# Modular-v1.net
KiCad netlist of a schematic drawn in EAGLE
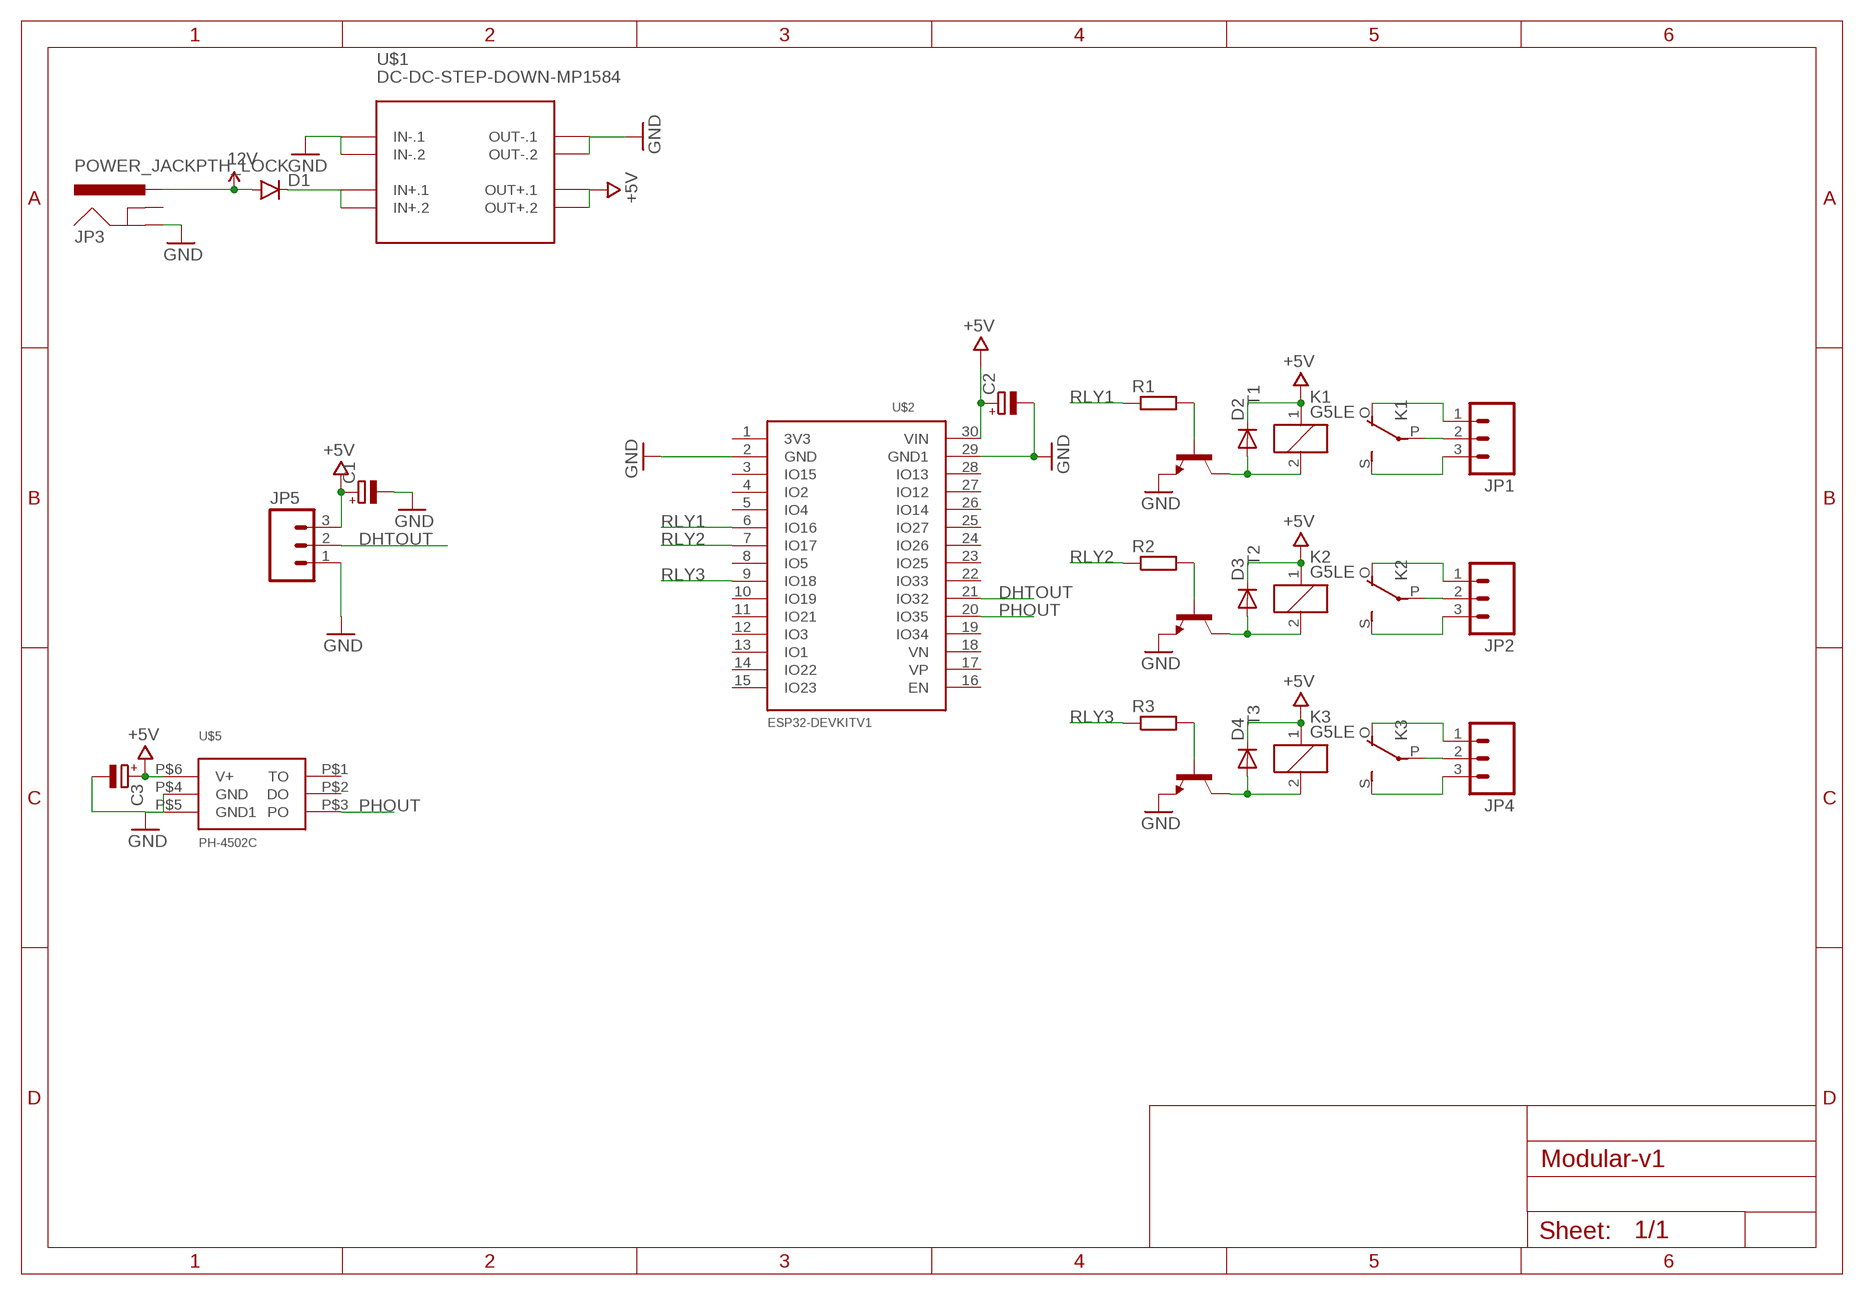
[diagram p0: schematic, sheet 1]

(export (version "E")
  (design (tool "Eeschema 10.0.6"))
  (components
    (comp (ref "C1")
      (value "CPOL-EUE5-5")
      (footprint "eagle-import:E5-5")
      (libsource (lib "eagle-import") (part "CPOL-EUE5-5"))
    )
    (comp (ref "C2")
      (value "CPOL-EUE5-13")
      (footprint "eagle-import:E5-13")
      (libsource (lib "eagle-import") (part "CPOL-EUE5-13"))
    )
    (comp (ref "C3")
      (value "CPOL-EUE5-8.5")
      (footprint "eagle-import:E5-8,5")
      (libsource (lib "eagle-import") (part "CPOL-EUE5-8.5"))
    )
    (comp (ref "D1")
      (value "DIODEKIT")
      (footprint "eagle-import:DIODE-1N4148-KIT")
      (libsource (lib "eagle-import") (part "DIODEKIT"))
    )
    (comp (ref "D2")
      (value "DIODE-D-2.5")
      (footprint "eagle-import:D-2.5")
      (libsource (lib "eagle-import") (part "DIODE-D-2.5"))
    )
    (comp (ref "D3")
      (value "DIODE-D-2.5")
      (footprint "eagle-import:D-2.5")
      (libsource (lib "eagle-import") (part "DIODE-D-2.5"))
    )
    (comp (ref "D4")
      (value "DIODE-D-2.5")
      (footprint "eagle-import:D-2.5")
      (libsource (lib "eagle-import") (part "DIODE-D-2.5"))
    )
    (comp (ref "JP1")
      (value "M03-SCREW-5MM")
      (footprint "eagle-import:SCREWTERMINAL-5MM-3")
      (libsource (lib "eagle-import") (part "M03-SCREW-5MM"))
    )
    (comp (ref "JP2")
      (value "M03-SCREW-5MM")
      (footprint "eagle-import:SCREWTERMINAL-5MM-3")
      (libsource (lib "eagle-import") (part "M03-SCREW-5MM"))
    )
    (comp (ref "JP3")
      (value "POWER_JACKPTH_LOCK")
      (footprint "eagle-import:POWER_JACK_PTH_LOCK")
      (libsource (lib "eagle-import") (part "POWER_JACKPTH_LOCK"))
    )
    (comp (ref "JP4")
      (value "M03-SCREW-5MM")
      (footprint "eagle-import:SCREWTERMINAL-5MM-3")
      (libsource (lib "eagle-import") (part "M03-SCREW-5MM"))
    )
    (comp (ref "JP5")
      (value "M03-SCREW-5MM")
      (footprint "eagle-import:SCREWTERMINAL-5MM-3")
      (libsource (lib "eagle-import") (part "M03-SCREW-5MM"))
    )
    (comp (ref "K1")
      (value "G5LE")
      (footprint "eagle-import:G5LE")
      (libsource (lib "eagle-import") (part "G5LE"))
    )
    (comp (ref "K2")
      (value "G5LE")
      (footprint "eagle-import:G5LE")
      (libsource (lib "eagle-import") (part "G5LE"))
    )
    (comp (ref "K3")
      (value "G5LE")
      (footprint "eagle-import:G5LE")
      (libsource (lib "eagle-import") (part "G5LE"))
    )
    (comp (ref "R1")
      (value "R-EU_R0805")
      (footprint "eagle-import:R0805")
      (libsource (lib "eagle-import") (part "R-EU_R0805"))
    )
    (comp (ref "R2")
      (value "R-EU_R0805")
      (footprint "eagle-import:R0805")
      (libsource (lib "eagle-import") (part "R-EU_R0805"))
    )
    (comp (ref "R3")
      (value "R-EU_R0805")
      (footprint "eagle-import:R0805")
      (libsource (lib "eagle-import") (part "R-EU_R0805"))
    )
    (comp (ref "T1")
      (value "-NPN-TO92-EBC")
      (footprint "eagle-import:TO92-EBC")
      (libsource (lib "eagle-import") (part "-NPN-TO92-EBC"))
    )
    (comp (ref "T2")
      (value "-NPN-TO92-EBC")
      (footprint "eagle-import:TO92-EBC")
      (libsource (lib "eagle-import") (part "-NPN-TO92-EBC"))
    )
    (comp (ref "T3")
      (value "-NPN-TO92-EBC")
      (footprint "eagle-import:TO92-EBC")
      (libsource (lib "eagle-import") (part "-NPN-TO92-EBC"))
    )
    (comp (ref "U$1")
      (value "DC-DC-STEP-DOWN-MP1584")
      (footprint "eagle-import:DC-DC-STEP-DOWN-MP1584")
      (libsource (lib "eagle-import") (part "DC-DC-STEP-DOWN-MP1584"))
    )
    (comp (ref "U$2")
      (value "ESP32DEVKITV1")
      (footprint "eagle-import:ESP32-DEVKITV1")
      (libsource (lib "eagle-import") (part "ESP32DEVKITV1"))
    )
    (comp (ref "U$5")
      (value "PH-4502C")
      (footprint "eagle-import:PH-4502C")
      (libsource (lib "eagle-import") (part "PH-4502C"))
    )
  )
  (nets
    (net (code "1") (name "+5V") (class "Default")
      (node (ref "C1") (pin "+") (pinfunction "+_+") (pintype "passive"))
      (node (ref "C2") (pin "+") (pinfunction "+_+") (pintype "passive"))
      (node (ref "C3") (pin "+") (pinfunction "+_+") (pintype "passive"))
      (node (ref "D2") (pin "C") (pinfunction "C_C") (pintype "passive"))
      (node (ref "D3") (pin "C") (pinfunction "C_C") (pintype "passive"))
      (node (ref "D4") (pin "C") (pinfunction "C_C") (pintype "passive"))
      (node (ref "JP5") (pin "3") (pinfunction "3_3") (pintype "passive"))
      (node (ref "K1") (pin "1") (pinfunction "1_1") (pintype "passive"))
      (node (ref "K2") (pin "1") (pinfunction "1_1") (pintype "passive"))
      (node (ref "K3") (pin "1") (pinfunction "1_1") (pintype "passive"))
      (node (ref "U$1") (pin "OUT+.1") (pinfunction "OUT+.1_OUT+.1") (pintype "bidirectional"))
      (node (ref "U$1") (pin "OUT+.2") (pinfunction "OUT+.2_OUT+.2") (pintype "bidirectional"))
      (node (ref "U$2") (pin "30") (pinfunction "VIN_30") (pintype "bidirectional"))
      (node (ref "U$5") (pin "P$6") (pinfunction "V+_P$6") (pintype "bidirectional"))
    )
    (net (code "2") (name "/DHTOUT") (class "Default")
      (node (ref "JP5") (pin "2") (pinfunction "2_2") (pintype "passive"))
      (node (ref "U$2") (pin "21") (pinfunction "IO32_21") (pintype "bidirectional"))
    )
    (net (code "3") (name "/PHOUT") (class "Default")
      (node (ref "U$2") (pin "20") (pinfunction "IO35_20") (pintype "bidirectional"))
      (node (ref "U$5") (pin "P$3") (pinfunction "PO_P$3") (pintype "bidirectional"))
    )
    (net (code "4") (name "/RLY1") (class "Default")
      (node (ref "R1") (pin "1") (pinfunction "1_1") (pintype "passive"))
      (node (ref "U$2") (pin "6") (pinfunction "IO16_6") (pintype "bidirectional"))
    )
    (net (code "5") (name "/RLY2") (class "Default")
      (node (ref "R2") (pin "1") (pinfunction "1_1") (pintype "passive"))
      (node (ref "U$2") (pin "7") (pinfunction "IO17_7") (pintype "bidirectional"))
    )
    (net (code "6") (name "/RLY3") (class "Default")
      (node (ref "R3") (pin "1") (pinfunction "1_1") (pintype "passive"))
      (node (ref "U$2") (pin "9") (pinfunction "IO18_9") (pintype "bidirectional"))
    )
    (net (code "7") (name "12V") (class "Default")
      (node (ref "D1") (pin "A") (pinfunction "A_A") (pintype "passive"))
      (node (ref "JP3") (pin "PWR") (pinfunction "PWR_PWR") (pintype "bidirectional"))
    )
    (net (code "8") (name "GND") (class "Default")
      (node (ref "C1") (pin "-") (pinfunction "-_-") (pintype "passive"))
      (node (ref "C2") (pin "-") (pinfunction "-_-") (pintype "passive"))
      (node (ref "C3") (pin "-") (pinfunction "-_-") (pintype "passive"))
      (node (ref "JP3") (pin "GND") (pinfunction "GND_GND") (pintype "bidirectional"))
      (node (ref "JP5") (pin "1") (pinfunction "1_1") (pintype "passive"))
      (node (ref "T1") (pin "E") (pinfunction "E_E") (pintype "passive"))
      (node (ref "T2") (pin "E") (pinfunction "E_E") (pintype "passive"))
      (node (ref "T3") (pin "E") (pinfunction "E_E") (pintype "passive"))
      (node (ref "U$1") (pin "IN-.1") (pinfunction "IN-.1_IN-.1") (pintype "bidirectional"))
      (node (ref "U$1") (pin "IN-.2") (pinfunction "IN-.2_IN-.2") (pintype "bidirectional"))
      (node (ref "U$1") (pin "OUT-.1") (pinfunction "OUT-.1_OUT-.1") (pintype "bidirectional"))
      (node (ref "U$1") (pin "OUT-.2") (pinfunction "OUT-.2_OUT-.2") (pintype "bidirectional"))
      (node (ref "U$2") (pin "2") (pinfunction "GND_2") (pintype "bidirectional"))
      (node (ref "U$2") (pin "29") (pinfunction "GND1_29") (pintype "bidirectional"))
      (node (ref "U$5") (pin "P$4") (pinfunction "GND_P$4") (pintype "bidirectional"))
      (node (ref "U$5") (pin "P$5") (pinfunction "GND1_P$5") (pintype "bidirectional"))
    )
    (net (code "9") (name "Net-(D1-PadC)") (class "Default")
      (node (ref "D1") (pin "C") (pinfunction "C_C") (pintype "passive"))
      (node (ref "U$1") (pin "IN+.1") (pinfunction "IN+.1_IN+.1") (pintype "bidirectional"))
      (node (ref "U$1") (pin "IN+.2") (pinfunction "IN+.2_IN+.2") (pintype "bidirectional"))
    )
    (net (code "10") (name "Net-(D2-PadA)") (class "Default")
      (node (ref "D2") (pin "A") (pinfunction "A_A") (pintype "passive"))
      (node (ref "K1") (pin "2") (pinfunction "2_2") (pintype "passive"))
      (node (ref "T1") (pin "C") (pinfunction "C_C") (pintype "passive"))
    )
    (net (code "11") (name "Net-(D3-PadA)") (class "Default")
      (node (ref "D3") (pin "A") (pinfunction "A_A") (pintype "passive"))
      (node (ref "K2") (pin "2") (pinfunction "2_2") (pintype "passive"))
      (node (ref "T2") (pin "C") (pinfunction "C_C") (pintype "passive"))
    )
    (net (code "12") (name "Net-(D4-PadA)") (class "Default")
      (node (ref "D4") (pin "A") (pinfunction "A_A") (pintype "passive"))
      (node (ref "K3") (pin "2") (pinfunction "2_2") (pintype "passive"))
      (node (ref "T3") (pin "C") (pinfunction "C_C") (pintype "passive"))
    )
    (net (code "13") (name "Net-(JP1-Pad1)") (class "Default")
      (node (ref "JP1") (pin "1") (pinfunction "1_1") (pintype "passive"))
      (node (ref "K1") (pin "O") (pinfunction "O_O") (pintype "passive"))
    )
    (net (code "14") (name "Net-(JP1-Pad2)") (class "Default")
      (node (ref "JP1") (pin "2") (pinfunction "2_2") (pintype "passive"))
      (node (ref "K1") (pin "P") (pinfunction "P_P") (pintype "passive"))
    )
    (net (code "15") (name "Net-(JP1-Pad3)") (class "Default")
      (node (ref "JP1") (pin "3") (pinfunction "3_3") (pintype "passive"))
      (node (ref "K1") (pin "S") (pinfunction "S_S") (pintype "passive"))
    )
    (net (code "16") (name "Net-(JP2-Pad1)") (class "Default")
      (node (ref "JP2") (pin "1") (pinfunction "1_1") (pintype "passive"))
      (node (ref "K2") (pin "O") (pinfunction "O_O") (pintype "passive"))
    )
    (net (code "17") (name "Net-(JP2-Pad2)") (class "Default")
      (node (ref "JP2") (pin "2") (pinfunction "2_2") (pintype "passive"))
      (node (ref "K2") (pin "P") (pinfunction "P_P") (pintype "passive"))
    )
    (net (code "18") (name "Net-(JP2-Pad3)") (class "Default")
      (node (ref "JP2") (pin "3") (pinfunction "3_3") (pintype "passive"))
      (node (ref "K2") (pin "S") (pinfunction "S_S") (pintype "passive"))
    )
    (net (code "19") (name "Net-(JP4-Pad1)") (class "Default")
      (node (ref "JP4") (pin "1") (pinfunction "1_1") (pintype "passive"))
      (node (ref "K3") (pin "O") (pinfunction "O_O") (pintype "passive"))
    )
    (net (code "20") (name "Net-(JP4-Pad2)") (class "Default")
      (node (ref "JP4") (pin "2") (pinfunction "2_2") (pintype "passive"))
      (node (ref "K3") (pin "P") (pinfunction "P_P") (pintype "passive"))
    )
    (net (code "21") (name "Net-(JP4-Pad3)") (class "Default")
      (node (ref "JP4") (pin "3") (pinfunction "3_3") (pintype "passive"))
      (node (ref "K3") (pin "S") (pinfunction "S_S") (pintype "passive"))
    )
    (net (code "22") (name "Net-(R1-Pad2)") (class "Default")
      (node (ref "R1") (pin "2") (pinfunction "2_2") (pintype "passive"))
      (node (ref "T1") (pin "B") (pinfunction "B_B") (pintype "passive"))
    )
    (net (code "23") (name "Net-(R2-Pad2)") (class "Default")
      (node (ref "R2") (pin "2") (pinfunction "2_2") (pintype "passive"))
      (node (ref "T2") (pin "B") (pinfunction "B_B") (pintype "passive"))
    )
    (net (code "24") (name "Net-(R3-Pad2)") (class "Default")
      (node (ref "R3") (pin "2") (pinfunction "2_2") (pintype "passive"))
      (node (ref "T3") (pin "B") (pinfunction "B_B") (pintype "passive"))
    )
    (net (code "25") (name "unconnected-(JP3-PadGNDBREAK)") (class "Default")
      (node (ref "JP3") (pin "GNDBREAK") (pinfunction "GNDBREAK_GNDBREAK") (pintype "bidirectional"))
    )
    (net (code "26") (name "unconnected-(U$2-3V3-Pad1)") (class "Default")
      (node (ref "U$2") (pin "1") (pinfunction "3V3_1") (pintype "bidirectional"))
    )
    (net (code "27") (name "unconnected-(U$2-EN-Pad16)") (class "Default")
      (node (ref "U$2") (pin "16") (pinfunction "EN_16") (pintype "bidirectional"))
    )
    (net (code "28") (name "unconnected-(U$2-IO1-Pad13)") (class "Default")
      (node (ref "U$2") (pin "13") (pinfunction "IO1_13") (pintype "bidirectional"))
    )
    (net (code "29") (name "unconnected-(U$2-IO2-Pad4)") (class "Default")
      (node (ref "U$2") (pin "4") (pinfunction "IO2_4") (pintype "bidirectional"))
    )
    (net (code "30") (name "unconnected-(U$2-IO3-Pad12)") (class "Default")
      (node (ref "U$2") (pin "12") (pinfunction "IO3_12") (pintype "bidirectional"))
    )
    (net (code "31") (name "unconnected-(U$2-IO4-Pad5)") (class "Default")
      (node (ref "U$2") (pin "5") (pinfunction "IO4_5") (pintype "bidirectional"))
    )
    (net (code "32") (name "unconnected-(U$2-IO5-Pad8)") (class "Default")
      (node (ref "U$2") (pin "8") (pinfunction "IO5_8") (pintype "bidirectional"))
    )
    (net (code "33") (name "unconnected-(U$2-IO12-Pad27)") (class "Default")
      (node (ref "U$2") (pin "27") (pinfunction "IO12_27") (pintype "bidirectional"))
    )
    (net (code "34") (name "unconnected-(U$2-IO13-Pad28)") (class "Default")
      (node (ref "U$2") (pin "28") (pinfunction "IO13_28") (pintype "bidirectional"))
    )
    (net (code "35") (name "unconnected-(U$2-IO14-Pad26)") (class "Default")
      (node (ref "U$2") (pin "26") (pinfunction "IO14_26") (pintype "bidirectional"))
    )
    (net (code "36") (name "unconnected-(U$2-IO15-Pad3)") (class "Default")
      (node (ref "U$2") (pin "3") (pinfunction "IO15_3") (pintype "bidirectional"))
    )
    (net (code "37") (name "unconnected-(U$2-IO19-Pad10)") (class "Default")
      (node (ref "U$2") (pin "10") (pinfunction "IO19_10") (pintype "bidirectional"))
    )
    (net (code "38") (name "unconnected-(U$2-IO21-Pad11)") (class "Default")
      (node (ref "U$2") (pin "11") (pinfunction "IO21_11") (pintype "bidirectional"))
    )
    (net (code "39") (name "unconnected-(U$2-IO22-Pad14)") (class "Default")
      (node (ref "U$2") (pin "14") (pinfunction "IO22_14") (pintype "bidirectional"))
    )
    (net (code "40") (name "unconnected-(U$2-IO23-Pad15)") (class "Default")
      (node (ref "U$2") (pin "15") (pinfunction "IO23_15") (pintype "bidirectional"))
    )
    (net (code "41") (name "unconnected-(U$2-IO25-Pad23)") (class "Default")
      (node (ref "U$2") (pin "23") (pinfunction "IO25_23") (pintype "bidirectional"))
    )
    (net (code "42") (name "unconnected-(U$2-IO26-Pad24)") (class "Default")
      (node (ref "U$2") (pin "24") (pinfunction "IO26_24") (pintype "bidirectional"))
    )
    (net (code "43") (name "unconnected-(U$2-IO27-Pad25)") (class "Default")
      (node (ref "U$2") (pin "25") (pinfunction "IO27_25") (pintype "bidirectional"))
    )
    (net (code "44") (name "unconnected-(U$2-IO33-Pad22)") (class "Default")
      (node (ref "U$2") (pin "22") (pinfunction "IO33_22") (pintype "bidirectional"))
    )
    (net (code "45") (name "unconnected-(U$2-IO34-Pad19)") (class "Default")
      (node (ref "U$2") (pin "19") (pinfunction "IO34_19") (pintype "bidirectional"))
    )
    (net (code "46") (name "unconnected-(U$2-VN-Pad18)") (class "Default")
      (node (ref "U$2") (pin "18") (pinfunction "VN_18") (pintype "bidirectional"))
    )
    (net (code "47") (name "unconnected-(U$2-VP-Pad17)") (class "Default")
      (node (ref "U$2") (pin "17") (pinfunction "VP_17") (pintype "bidirectional"))
    )
    (net (code "48") (name "unconnected-(U$5-DO-PadP$2)") (class "Default")
      (node (ref "U$5") (pin "P$2") (pinfunction "DO_P$2") (pintype "bidirectional"))
    )
    (net (code "49") (name "unconnected-(U$5-TO-PadP$1)") (class "Default")
      (node (ref "U$5") (pin "P$1") (pinfunction "TO_P$1") (pintype "bidirectional"))
    )
  )
)
